# ZigBeeModule.net
KiCad netlist of a schematic drawn in EAGLE
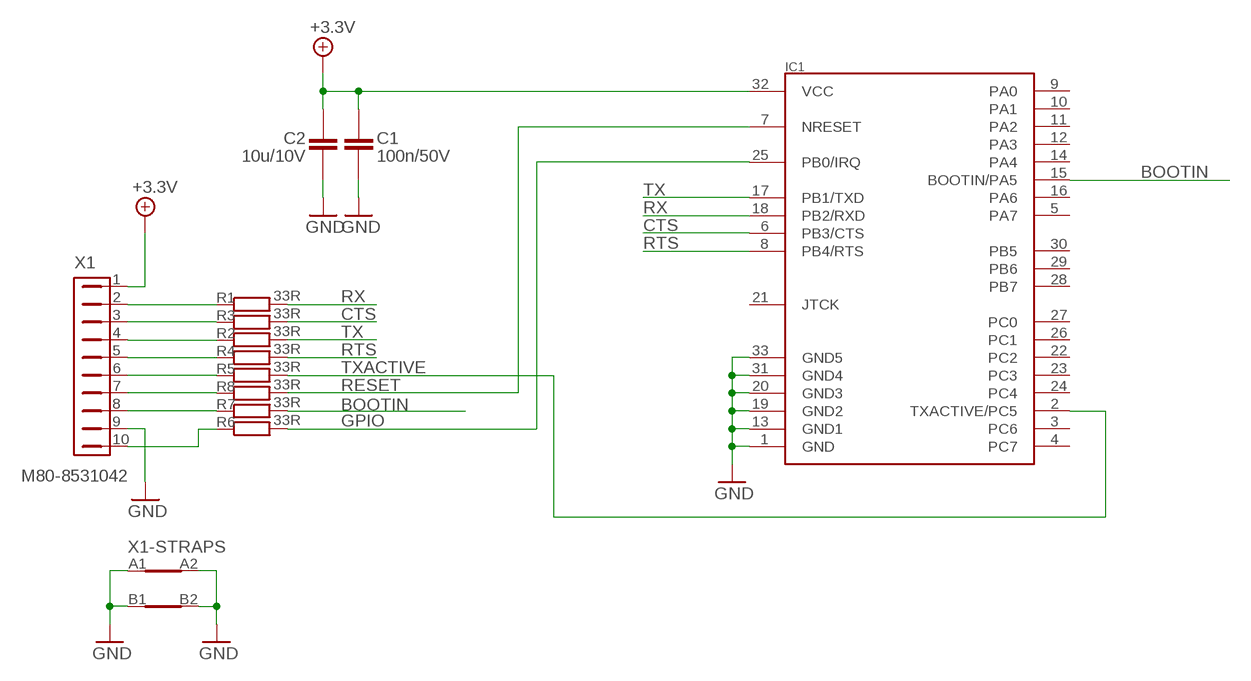
[diagram p0: schematic, sheet 1]

(export (version "E")
  (design (tool "Eeschema 10.0.6"))
  (components
    (comp (ref "C1")
      (value "100N/50V,X7R,+/-10%_0603R")
      (footprint "eagle-import:C0603R")
      (libsource (lib "eagle-import") (part "100N_0603R/50V,X7R,+/-10%"))
    )
    (comp (ref "C2")
      (value "10U/10V,X5R,+/-20%_0603R")
      (footprint "eagle-import:C0603R")
      (libsource (lib "eagle-import") (part "10U_0603R/10V,X5R,+/-20%"))
    )
    (comp (ref "IC1")
      (value "ETRX357")
      (footprint "eagle-import:ETRX3")
      (libsource (lib "eagle-import") (part "ETRX357"))
    )
    (comp (ref "R1")
      (value "33R/0.1W,THICK_FILM,1%_0603R")
      (footprint "eagle-import:R0603R")
      (fields (field (name "COMPONENT_VALUE") "33R"))
      (libsource (lib "eagle-import") (part "33R_0603R/0.1W,THICK_FILM,1%"))
    )
    (comp (ref "R2")
      (value "33R/0.1W,THICK_FILM,1%_0603R")
      (footprint "eagle-import:R0603R")
      (fields (field (name "COMPONENT_VALUE") "33R"))
      (libsource (lib "eagle-import") (part "33R_0603R/0.1W,THICK_FILM,1%"))
    )
    (comp (ref "R3")
      (value "33R/0.1W,THICK_FILM,1%_0603R")
      (footprint "eagle-import:R0603R")
      (fields (field (name "COMPONENT_VALUE") "33R"))
      (libsource (lib "eagle-import") (part "33R_0603R/0.1W,THICK_FILM,1%"))
    )
    (comp (ref "R4")
      (value "33R/0.1W,THICK_FILM,1%_0603R")
      (footprint "eagle-import:R0603R")
      (fields (field (name "COMPONENT_VALUE") "33R"))
      (libsource (lib "eagle-import") (part "33R_0603R/0.1W,THICK_FILM,1%"))
    )
    (comp (ref "R5")
      (value "33R/0.1W,THICK_FILM,1%_0603R")
      (footprint "eagle-import:R0603R")
      (fields (field (name "COMPONENT_VALUE") "33R"))
      (libsource (lib "eagle-import") (part "33R_0603R/0.1W,THICK_FILM,1%"))
    )
    (comp (ref "R6")
      (value "33R/0.1W,THICK_FILM,1%_0603R")
      (footprint "eagle-import:R0603R")
      (fields (field (name "COMPONENT_VALUE") "33R"))
      (libsource (lib "eagle-import") (part "33R_0603R/0.1W,THICK_FILM,1%"))
    )
    (comp (ref "R7")
      (value "33R/0.1W,THICK_FILM,1%_0603R")
      (footprint "eagle-import:R0603R")
      (fields (field (name "COMPONENT_VALUE") "33R"))
      (libsource (lib "eagle-import") (part "33R_0603R/0.1W,THICK_FILM,1%"))
    )
    (comp (ref "R8")
      (value "33R/0.1W,THICK_FILM,1%_0603R")
      (footprint "eagle-import:R0603R")
      (fields (field (name "COMPONENT_VALUE") "33R"))
      (libsource (lib "eagle-import") (part "33R_0603R/0.1W,THICK_FILM,1%"))
    )
    (comp (ref "X1")
      (value "M80-8531042")
      (footprint "eagle-import:M80-85310-W_STRAPS")
      (fields (field (name "COMPONENT_VALUE") "M80-8531042"))
      (libsource (lib "eagle-import") (part "M80-?1042-W_STRAPS853"))
    )
  )
  (nets
    (net (code "1") (name "+3.3V") (class "Default")
      (node (ref "C1") (pin "2") (pinfunction "2_2") (pintype "passive"))
      (node (ref "C2") (pin "2") (pinfunction "2_2") (pintype "passive"))
      (node (ref "IC1") (pin "32") (pinfunction "VCC_32") (pintype "bidirectional"))
      (node (ref "X1") (pin "1") (pinfunction "1_1") (pintype "passive"))
    )
    (net (code "2") (name "/BOOTIN") (class "Default")
      (node (ref "IC1") (pin "15") (pinfunction "BOOTIN/PA5_15") (pintype "bidirectional"))
      (node (ref "R7") (pin "2") (pinfunction "2_2") (pintype "passive"))
    )
    (net (code "3") (name "/CTS") (class "Default")
      (node (ref "IC1") (pin "6") (pinfunction "PB3/CTS_6") (pintype "bidirectional"))
      (node (ref "R3") (pin "2") (pinfunction "2_2") (pintype "passive"))
    )
    (net (code "4") (name "/GPIO") (class "Default")
      (node (ref "IC1") (pin "25") (pinfunction "PB0/IRQ_25") (pintype "bidirectional"))
      (node (ref "R6") (pin "2") (pinfunction "2_2") (pintype "passive"))
    )
    (net (code "5") (name "/RESET") (class "Default")
      (node (ref "IC1") (pin "7") (pinfunction "NRESET_7") (pintype "bidirectional"))
      (node (ref "R8") (pin "2") (pinfunction "2_2") (pintype "passive"))
    )
    (net (code "6") (name "/RTS") (class "Default")
      (node (ref "IC1") (pin "8") (pinfunction "PB4/RTS_8") (pintype "bidirectional"))
      (node (ref "R4") (pin "2") (pinfunction "2_2") (pintype "passive"))
    )
    (net (code "7") (name "/RX") (class "Default")
      (node (ref "IC1") (pin "18") (pinfunction "PB2/RXD_18") (pintype "bidirectional"))
      (node (ref "R1") (pin "2") (pinfunction "2_2") (pintype "passive"))
    )
    (net (code "8") (name "/TX") (class "Default")
      (node (ref "IC1") (pin "17") (pinfunction "PB1/TXD_17") (pintype "bidirectional"))
      (node (ref "R2") (pin "2") (pinfunction "2_2") (pintype "passive"))
    )
    (net (code "9") (name "/TXACTIVE") (class "Default")
      (node (ref "IC1") (pin "2") (pinfunction "TXACTIVE/PC5_2") (pintype "bidirectional"))
      (node (ref "R5") (pin "2") (pinfunction "2_2") (pintype "passive"))
    )
    (net (code "10") (name "GND") (class "Default")
      (node (ref "C1") (pin "1") (pinfunction "1_1") (pintype "passive"))
      (node (ref "C2") (pin "1") (pinfunction "1_1") (pintype "passive"))
      (node (ref "IC1") (pin "1") (pinfunction "GND_1") (pintype "bidirectional"))
      (node (ref "IC1") (pin "13") (pinfunction "GND1_13") (pintype "bidirectional"))
      (node (ref "IC1") (pin "19") (pinfunction "GND2_19") (pintype "bidirectional"))
      (node (ref "IC1") (pin "20") (pinfunction "GND3_20") (pintype "bidirectional"))
      (node (ref "IC1") (pin "31") (pinfunction "GND4_31") (pintype "bidirectional"))
      (node (ref "IC1") (pin "33") (pinfunction "GND5_33") (pintype "bidirectional"))
      (node (ref "X1") (pin "9") (pinfunction "9_9") (pintype "passive"))
      (node (ref "X1") (pin "A1") (pinfunction "A1_A1") (pintype "passive"))
      (node (ref "X1") (pin "A2") (pinfunction "A2_A2") (pintype "passive"))
      (node (ref "X1") (pin "B1") (pinfunction "B1_B1") (pintype "passive"))
      (node (ref "X1") (pin "B2") (pinfunction "B2_B2") (pintype "passive"))
    )
    (net (code "11") (name "Net-(R1-Pad1)") (class "Default")
      (node (ref "R1") (pin "1") (pinfunction "1_1") (pintype "passive"))
      (node (ref "X1") (pin "2") (pinfunction "2_2") (pintype "passive"))
    )
    (net (code "12") (name "Net-(R2-Pad1)") (class "Default")
      (node (ref "R2") (pin "1") (pinfunction "1_1") (pintype "passive"))
      (node (ref "X1") (pin "4") (pinfunction "4_4") (pintype "passive"))
    )
    (net (code "13") (name "Net-(R3-Pad1)") (class "Default")
      (node (ref "R3") (pin "1") (pinfunction "1_1") (pintype "passive"))
      (node (ref "X1") (pin "3") (pinfunction "3_3") (pintype "passive"))
    )
    (net (code "14") (name "Net-(R4-Pad1)") (class "Default")
      (node (ref "R4") (pin "1") (pinfunction "1_1") (pintype "passive"))
      (node (ref "X1") (pin "5") (pinfunction "5_5") (pintype "passive"))
    )
    (net (code "15") (name "Net-(R5-Pad1)") (class "Default")
      (node (ref "R5") (pin "1") (pinfunction "1_1") (pintype "passive"))
      (node (ref "X1") (pin "6") (pinfunction "6_6") (pintype "passive"))
    )
    (net (code "16") (name "Net-(R6-Pad1)") (class "Default")
      (node (ref "R6") (pin "1") (pinfunction "1_1") (pintype "passive"))
      (node (ref "X1") (pin "10") (pinfunction "10_10") (pintype "passive"))
    )
    (net (code "17") (name "Net-(R7-Pad1)") (class "Default")
      (node (ref "R7") (pin "1") (pinfunction "1_1") (pintype "passive"))
      (node (ref "X1") (pin "8") (pinfunction "8_8") (pintype "passive"))
    )
    (net (code "18") (name "Net-(R8-Pad1)") (class "Default")
      (node (ref "R8") (pin "1") (pinfunction "1_1") (pintype "passive"))
      (node (ref "X1") (pin "7") (pinfunction "7_7") (pintype "passive"))
    )
    (net (code "19") (name "unconnected-(IC1-JTCK-Pad21)") (class "Default")
      (node (ref "IC1") (pin "21") (pinfunction "JTCK_21") (pintype "bidirectional"))
    )
    (net (code "20") (name "unconnected-(IC1-PA0-Pad9)") (class "Default")
      (node (ref "IC1") (pin "9") (pinfunction "PA0_9") (pintype "bidirectional"))
    )
    (net (code "21") (name "unconnected-(IC1-PA1-Pad10)") (class "Default")
      (node (ref "IC1") (pin "10") (pinfunction "PA1_10") (pintype "bidirectional"))
    )
    (net (code "22") (name "unconnected-(IC1-PA2-Pad11)") (class "Default")
      (node (ref "IC1") (pin "11") (pinfunction "PA2_11") (pintype "bidirectional"))
    )
    (net (code "23") (name "unconnected-(IC1-PA3-Pad12)") (class "Default")
      (node (ref "IC1") (pin "12") (pinfunction "PA3_12") (pintype "bidirectional"))
    )
    (net (code "24") (name "unconnected-(IC1-PA4-Pad14)") (class "Default")
      (node (ref "IC1") (pin "14") (pinfunction "PA4_14") (pintype "bidirectional"))
    )
    (net (code "25") (name "unconnected-(IC1-PA6-Pad16)") (class "Default")
      (node (ref "IC1") (pin "16") (pinfunction "PA6_16") (pintype "bidirectional"))
    )
    (net (code "26") (name "unconnected-(IC1-PA7-Pad5)") (class "Default")
      (node (ref "IC1") (pin "5") (pinfunction "PA7_5") (pintype "bidirectional"))
    )
    (net (code "27") (name "unconnected-(IC1-PB5-Pad30)") (class "Default")
      (node (ref "IC1") (pin "30") (pinfunction "PB5_30") (pintype "bidirectional"))
    )
    (net (code "28") (name "unconnected-(IC1-PB6-Pad29)") (class "Default")
      (node (ref "IC1") (pin "29") (pinfunction "PB6_29") (pintype "bidirectional"))
    )
    (net (code "29") (name "unconnected-(IC1-PB7-Pad28)") (class "Default")
      (node (ref "IC1") (pin "28") (pinfunction "PB7_28") (pintype "bidirectional"))
    )
    (net (code "30") (name "unconnected-(IC1-PC0-Pad27)") (class "Default")
      (node (ref "IC1") (pin "27") (pinfunction "PC0_27") (pintype "bidirectional"))
    )
    (net (code "31") (name "unconnected-(IC1-PC1-Pad26)") (class "Default")
      (node (ref "IC1") (pin "26") (pinfunction "PC1_26") (pintype "bidirectional"))
    )
    (net (code "32") (name "unconnected-(IC1-PC2-Pad22)") (class "Default")
      (node (ref "IC1") (pin "22") (pinfunction "PC2_22") (pintype "bidirectional"))
    )
    (net (code "33") (name "unconnected-(IC1-PC3-Pad23)") (class "Default")
      (node (ref "IC1") (pin "23") (pinfunction "PC3_23") (pintype "bidirectional"))
    )
    (net (code "34") (name "unconnected-(IC1-PC4-Pad24)") (class "Default")
      (node (ref "IC1") (pin "24") (pinfunction "PC4_24") (pintype "bidirectional"))
    )
    (net (code "35") (name "unconnected-(IC1-PC6-Pad3)") (class "Default")
      (node (ref "IC1") (pin "3") (pinfunction "PC6_3") (pintype "bidirectional"))
    )
    (net (code "36") (name "unconnected-(IC1-PC7-Pad4)") (class "Default")
      (node (ref "IC1") (pin "4") (pinfunction "PC7_4") (pintype "bidirectional"))
    )
  )
)
